# BaseBoard.net
KiCad netlist of a schematic drawn in EAGLE
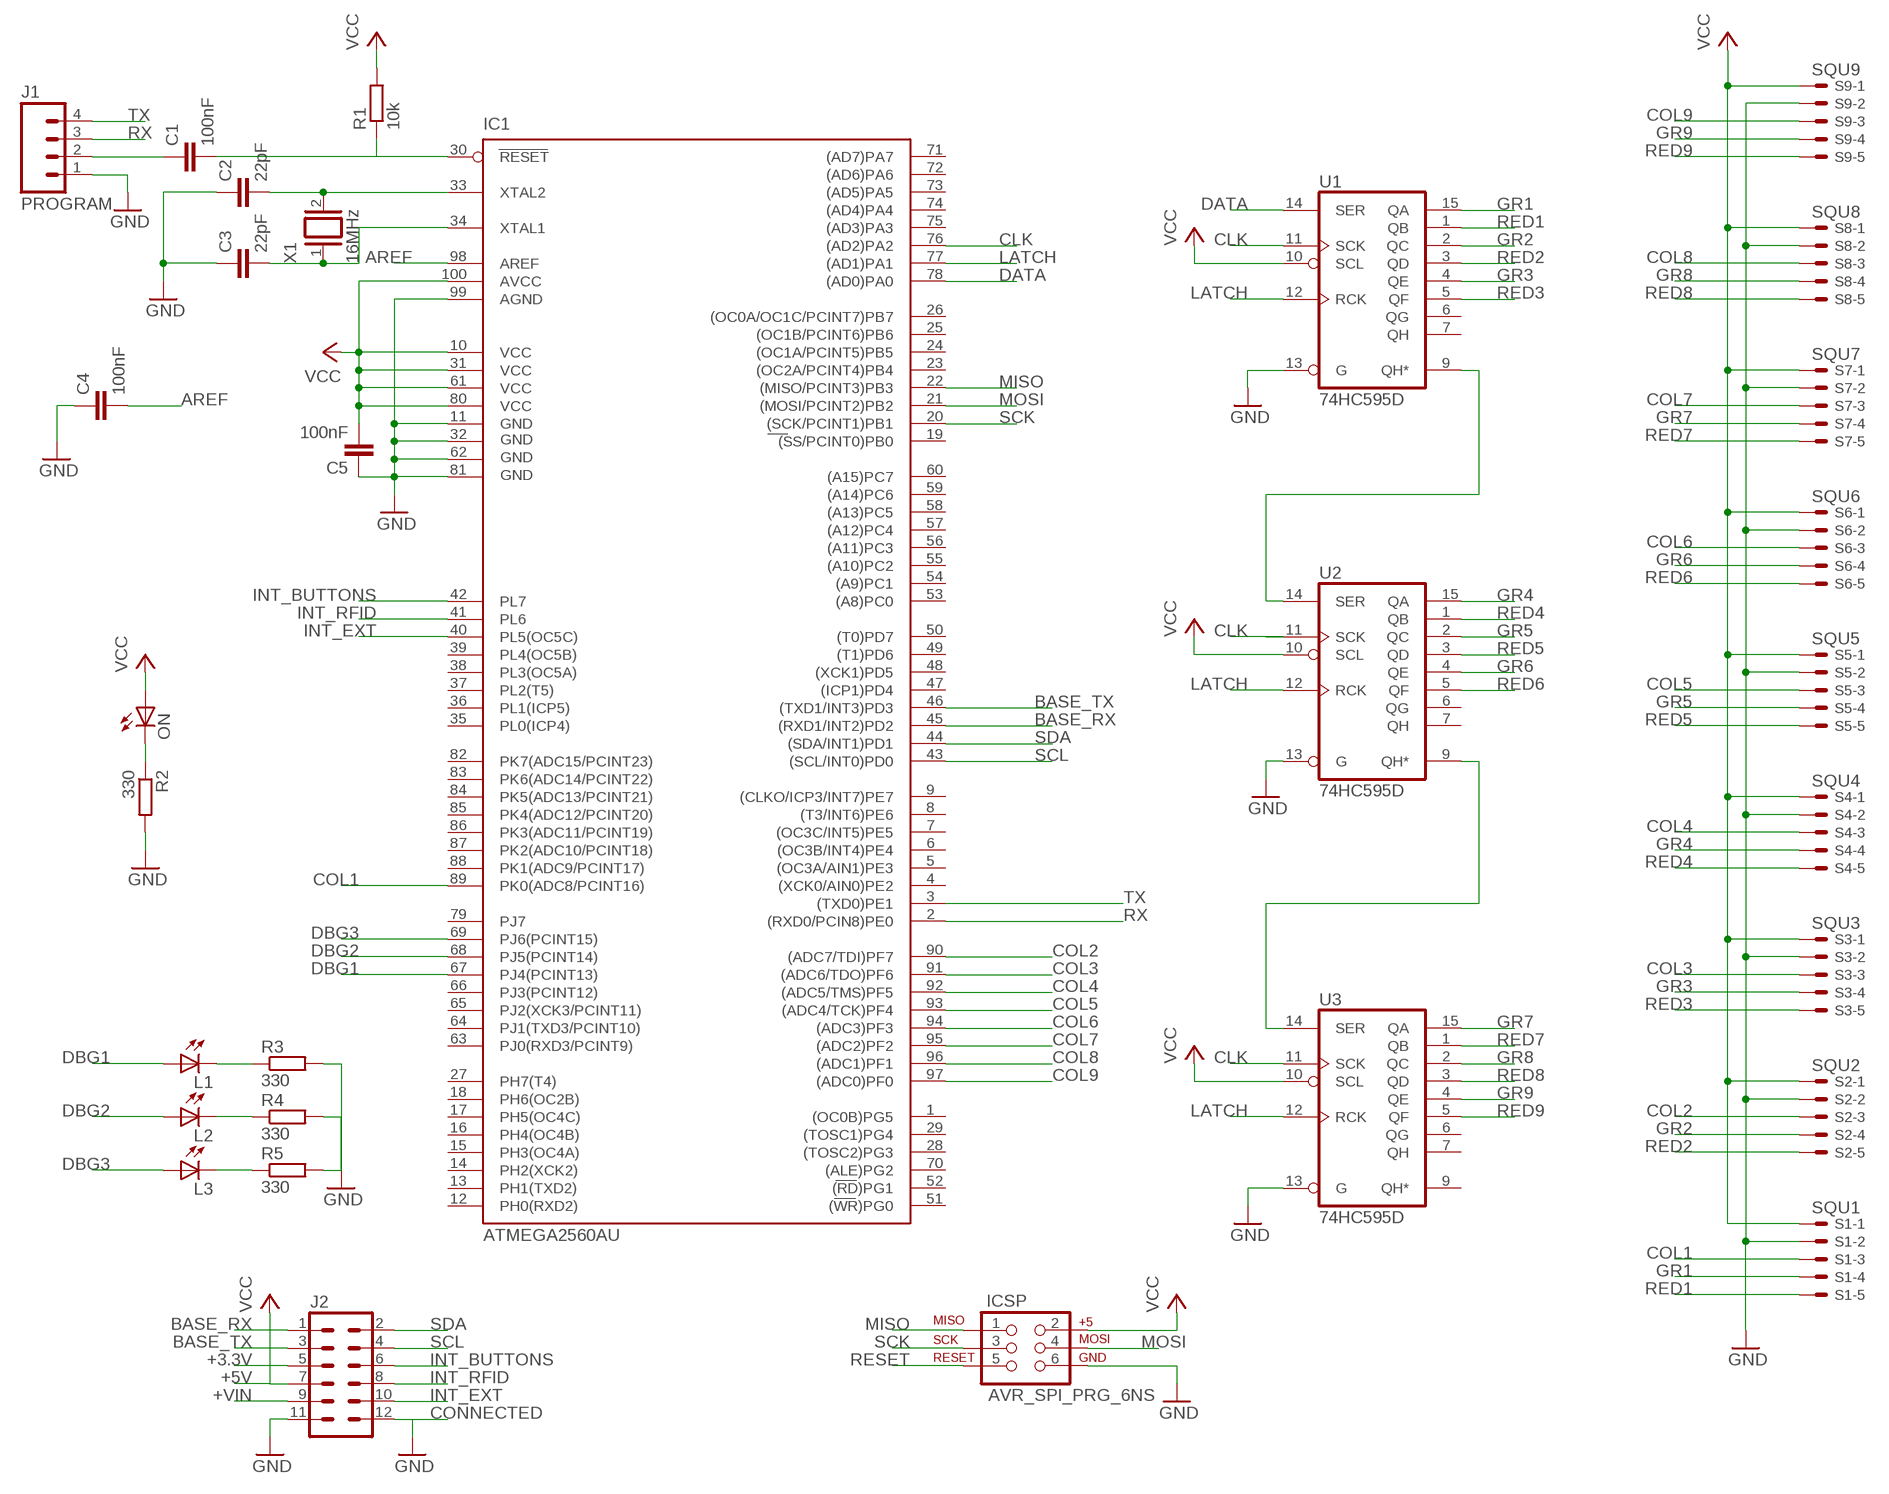
[diagram p0: schematic, sheet 1]

(export (version "E")
  (design (tool "Eeschema 10.0.6"))
  (components
    (comp (ref "C1")
      (value "100nF")
      (footprint "eagle-import:C0805")
      (libsource (lib "eagle-import") (part "C-EUC0805"))
    )
    (comp (ref "C2")
      (value "22pF")
      (footprint "eagle-import:C0805")
      (libsource (lib "eagle-import") (part "C-EUC0805"))
    )
    (comp (ref "C3")
      (value "22pF")
      (footprint "eagle-import:C0805")
      (libsource (lib "eagle-import") (part "C-EUC0805"))
    )
    (comp (ref "C4")
      (value "100nF")
      (footprint "eagle-import:C0805")
      (libsource (lib "eagle-import") (part "C-EUC0805"))
    )
    (comp (ref "C5")
      (value "100nF")
      (footprint "eagle-import:C0805")
      (libsource (lib "eagle-import") (part "C-EUC0805"))
    )
    (comp (ref "IC1")
      (value "ATMEGA2560AU")
      (footprint "eagle-import:TQFP100")
      (libsource (lib "eagle-import") (part "ATMEGA2560AU"))
    )
    (comp (ref "ICSP")
      (value "AVR_SPI_PRG_6NS")
      (footprint "eagle-import:2X3-NS")
      (libsource (lib "eagle-import") (part "AVR_SPI_PRG_6NS"))
    )
    (comp (ref "J1")
      (value "PROGRAM")
      (footprint "eagle-import:1X04")
      (libsource (lib "eagle-import") (part "M04PTH"))
    )
    (comp (ref "J2")
      (value "CON06X2-2MM")
      (footprint "eagle-import:CON06X2_2MM")
      (libsource (lib "eagle-import") (part "CON06X2-2MM"))
    )
    (comp (ref "L1")
      (value "LEDCHIP-LED0805")
      (footprint "eagle-import:CHIP-LED0805")
      (libsource (lib "eagle-import") (part "LEDCHIP-LED0805"))
    )
    (comp (ref "L2")
      (value "LEDCHIP-LED0805")
      (footprint "eagle-import:CHIP-LED0805")
      (libsource (lib "eagle-import") (part "LEDCHIP-LED0805"))
    )
    (comp (ref "L3")
      (value "LEDCHIP-LED0805")
      (footprint "eagle-import:CHIP-LED0805")
      (libsource (lib "eagle-import") (part "LEDCHIP-LED0805"))
    )
    (comp (ref "ON")
      (value "LEDCHIP-LED0805")
      (footprint "eagle-import:CHIP-LED0805")
      (libsource (lib "eagle-import") (part "LEDCHIP-LED0805"))
    )
    (comp (ref "R1")
      (value "10k")
      (footprint "eagle-import:R0805")
      (libsource (lib "eagle-import") (part "R-EU_R0805"))
    )
    (comp (ref "R2")
      (value "330")
      (footprint "eagle-import:R0805")
      (libsource (lib "eagle-import") (part "R-EU_R0805"))
    )
    (comp (ref "R3")
      (value "330")
      (footprint "eagle-import:R0805")
      (libsource (lib "eagle-import") (part "R-EU_R0805"))
    )
    (comp (ref "R4")
      (value "330")
      (footprint "eagle-import:R0805")
      (libsource (lib "eagle-import") (part "R-EU_R0805"))
    )
    (comp (ref "R5")
      (value "330")
      (footprint "eagle-import:R0805")
      (libsource (lib "eagle-import") (part "R-EU_R0805"))
    )
    (comp (ref "S1")
      (value "SQU1")
      (footprint "eagle-import:53261-05")
      (libsource (lib "eagle-import") (part "53?-05261"))
    )
    (comp (ref "S2")
      (value "SQU2")
      (footprint "eagle-import:53261-05")
      (libsource (lib "eagle-import") (part "53?-05261"))
    )
    (comp (ref "S3")
      (value "SQU3")
      (footprint "eagle-import:53261-05")
      (libsource (lib "eagle-import") (part "53?-05261"))
    )
    (comp (ref "S4")
      (value "SQU4")
      (footprint "eagle-import:53261-05")
      (libsource (lib "eagle-import") (part "53?-05261"))
    )
    (comp (ref "S5")
      (value "SQU5")
      (footprint "eagle-import:53261-05")
      (libsource (lib "eagle-import") (part "53?-05261"))
    )
    (comp (ref "S6")
      (value "SQU6")
      (footprint "eagle-import:53261-05")
      (libsource (lib "eagle-import") (part "53?-05261"))
    )
    (comp (ref "S7")
      (value "SQU7")
      (footprint "eagle-import:53261-05")
      (libsource (lib "eagle-import") (part "53?-05261"))
    )
    (comp (ref "S8")
      (value "SQU8")
      (footprint "eagle-import:53261-05")
      (libsource (lib "eagle-import") (part "53?-05261"))
    )
    (comp (ref "S9")
      (value "SQU9")
      (footprint "eagle-import:53261-05")
      (libsource (lib "eagle-import") (part "53?-05261"))
    )
    (comp (ref "U1")
      (value "74HC595D")
      (footprint "eagle-import:SO16")
      (libsource (lib "eagle-import") (part "74595DHC"))
    )
    (comp (ref "U2")
      (value "74HC595D")
      (footprint "eagle-import:SO16")
      (libsource (lib "eagle-import") (part "74595DHC"))
    )
    (comp (ref "U3")
      (value "74HC595D")
      (footprint "eagle-import:SO16")
      (libsource (lib "eagle-import") (part "74595DHC"))
    )
    (comp (ref "X1")
      (value "16MHz")
      (footprint "eagle-import:QS")
      (libsource (lib "eagle-import") (part "XTAL/S"))
    )
  )
  (nets
    (net (code "1") (name "/+3.3V") (class "Default")
      (node (ref "J2") (pin "5") (pinfunction "5_5") (pintype "passive"))
    )
    (net (code "2") (name "/+VIN") (class "Default")
      (node (ref "J2") (pin "9") (pinfunction "9_9") (pintype "passive"))
    )
    (net (code "3") (name "/AREF") (class "Default")
      (node (ref "C4") (pin "2") (pinfunction "2_2") (pintype "passive"))
      (node (ref "IC1") (pin "98") (pinfunction "AREF_98") (pintype "bidirectional"))
    )
    (net (code "4") (name "/BASE_RX") (class "Default")
      (node (ref "IC1") (pin "45") (pinfunction "(RXD1/INT2)PD2_45") (pintype "bidirectional"))
      (node (ref "J2") (pin "1") (pinfunction "1_1") (pintype "passive"))
    )
    (net (code "5") (name "/BASE_TX") (class "Default")
      (node (ref "IC1") (pin "46") (pinfunction "(TXD1/INT3)PD3_46") (pintype "bidirectional"))
      (node (ref "J2") (pin "3") (pinfunction "3_3") (pintype "passive"))
    )
    (net (code "6") (name "/CLK") (class "Default")
      (node (ref "IC1") (pin "76") (pinfunction "(AD2)PA2_76") (pintype "bidirectional"))
      (node (ref "U1") (pin "11") (pinfunction "SCK_11") (pintype "input"))
      (node (ref "U2") (pin "11") (pinfunction "SCK_11") (pintype "input"))
      (node (ref "U3") (pin "11") (pinfunction "SCK_11") (pintype "input"))
    )
    (net (code "7") (name "/COL1") (class "Default")
      (node (ref "IC1") (pin "89") (pinfunction "PK0(ADC8/PCINT16)_89") (pintype "bidirectional"))
      (node (ref "S1") (pin "3") (pinfunction "S_3") (pintype "passive"))
    )
    (net (code "8") (name "/COL2") (class "Default")
      (node (ref "IC1") (pin "90") (pinfunction "(ADC7/TDI)PF7_90") (pintype "bidirectional"))
      (node (ref "S2") (pin "3") (pinfunction "S_3") (pintype "passive"))
    )
    (net (code "9") (name "/COL3") (class "Default")
      (node (ref "IC1") (pin "91") (pinfunction "(ADC6/TDO)PF6_91") (pintype "bidirectional"))
      (node (ref "S3") (pin "3") (pinfunction "S_3") (pintype "passive"))
    )
    (net (code "10") (name "/COL4") (class "Default")
      (node (ref "IC1") (pin "92") (pinfunction "(ADC5/TMS)PF5_92") (pintype "bidirectional"))
      (node (ref "S4") (pin "3") (pinfunction "S_3") (pintype "passive"))
    )
    (net (code "11") (name "/COL5") (class "Default")
      (node (ref "IC1") (pin "93") (pinfunction "(ADC4/TCK)PF4_93") (pintype "bidirectional"))
      (node (ref "S5") (pin "3") (pinfunction "S_3") (pintype "passive"))
    )
    (net (code "12") (name "/COL6") (class "Default")
      (node (ref "IC1") (pin "94") (pinfunction "(ADC3)PF3_94") (pintype "bidirectional"))
      (node (ref "S6") (pin "3") (pinfunction "S_3") (pintype "passive"))
    )
    (net (code "13") (name "/COL7") (class "Default")
      (node (ref "IC1") (pin "95") (pinfunction "(ADC2)PF2_95") (pintype "bidirectional"))
      (node (ref "S7") (pin "3") (pinfunction "S_3") (pintype "passive"))
    )
    (net (code "14") (name "/COL8") (class "Default")
      (node (ref "IC1") (pin "96") (pinfunction "(ADC1)PF1_96") (pintype "bidirectional"))
      (node (ref "S8") (pin "3") (pinfunction "S_3") (pintype "passive"))
    )
    (net (code "15") (name "/COL9") (class "Default")
      (node (ref "IC1") (pin "97") (pinfunction "(ADC0)PF0_97") (pintype "bidirectional"))
      (node (ref "S9") (pin "3") (pinfunction "S_3") (pintype "passive"))
    )
    (net (code "16") (name "/DATA") (class "Default")
      (node (ref "IC1") (pin "78") (pinfunction "(AD0)PA0_78") (pintype "bidirectional"))
      (node (ref "U1") (pin "14") (pinfunction "SER_14") (pintype "input"))
    )
    (net (code "17") (name "/DBG1") (class "Default")
      (node (ref "IC1") (pin "67") (pinfunction "PJ4(PCINT13)_67") (pintype "bidirectional"))
      (node (ref "L1") (pin "A") (pinfunction "A_A") (pintype "passive"))
    )
    (net (code "18") (name "/DBG2") (class "Default")
      (node (ref "IC1") (pin "68") (pinfunction "PJ5(PCINT14)_68") (pintype "bidirectional"))
      (node (ref "L2") (pin "A") (pinfunction "A_A") (pintype "passive"))
    )
    (net (code "19") (name "/DBG3") (class "Default")
      (node (ref "IC1") (pin "69") (pinfunction "PJ6(PCINT15)_69") (pintype "bidirectional"))
      (node (ref "L3") (pin "A") (pinfunction "A_A") (pintype "passive"))
    )
    (net (code "20") (name "/GR1") (class "Default")
      (node (ref "S1") (pin "4") (pinfunction "S_4") (pintype "passive"))
      (node (ref "U1") (pin "15") (pinfunction "QA_15") (pintype "tri_state"))
    )
    (net (code "21") (name "/GR2") (class "Default")
      (node (ref "S2") (pin "4") (pinfunction "S_4") (pintype "passive"))
      (node (ref "U1") (pin "2") (pinfunction "QC_2") (pintype "tri_state"))
    )
    (net (code "22") (name "/GR3") (class "Default")
      (node (ref "S3") (pin "4") (pinfunction "S_4") (pintype "passive"))
      (node (ref "U1") (pin "4") (pinfunction "QE_4") (pintype "tri_state"))
    )
    (net (code "23") (name "/GR4") (class "Default")
      (node (ref "S4") (pin "4") (pinfunction "S_4") (pintype "passive"))
      (node (ref "U2") (pin "15") (pinfunction "QA_15") (pintype "tri_state"))
    )
    (net (code "24") (name "/GR5") (class "Default")
      (node (ref "S5") (pin "4") (pinfunction "S_4") (pintype "passive"))
      (node (ref "U2") (pin "2") (pinfunction "QC_2") (pintype "tri_state"))
    )
    (net (code "25") (name "/GR6") (class "Default")
      (node (ref "S6") (pin "4") (pinfunction "S_4") (pintype "passive"))
      (node (ref "U2") (pin "4") (pinfunction "QE_4") (pintype "tri_state"))
    )
    (net (code "26") (name "/GR7") (class "Default")
      (node (ref "S7") (pin "4") (pinfunction "S_4") (pintype "passive"))
      (node (ref "U3") (pin "15") (pinfunction "QA_15") (pintype "tri_state"))
    )
    (net (code "27") (name "/GR8") (class "Default")
      (node (ref "S8") (pin "4") (pinfunction "S_4") (pintype "passive"))
      (node (ref "U3") (pin "2") (pinfunction "QC_2") (pintype "tri_state"))
    )
    (net (code "28") (name "/GR9") (class "Default")
      (node (ref "S9") (pin "4") (pinfunction "S_4") (pintype "passive"))
      (node (ref "U3") (pin "4") (pinfunction "QE_4") (pintype "tri_state"))
    )
    (net (code "29") (name "/INT_BUTTONS") (class "Default")
      (node (ref "IC1") (pin "42") (pinfunction "PL7_42") (pintype "bidirectional"))
      (node (ref "J2") (pin "6") (pinfunction "6_6") (pintype "passive"))
    )
    (net (code "30") (name "/INT_EXT") (class "Default")
      (node (ref "IC1") (pin "40") (pinfunction "PL5(OC5C)_40") (pintype "bidirectional"))
      (node (ref "J2") (pin "10") (pinfunction "10_10") (pintype "passive"))
    )
    (net (code "31") (name "/INT_RFID") (class "Default")
      (node (ref "IC1") (pin "41") (pinfunction "PL6_41") (pintype "bidirectional"))
      (node (ref "J2") (pin "8") (pinfunction "8_8") (pintype "passive"))
    )
    (net (code "32") (name "/LATCH") (class "Default")
      (node (ref "IC1") (pin "77") (pinfunction "(AD1)PA1_77") (pintype "bidirectional"))
      (node (ref "U1") (pin "12") (pinfunction "RCK_12") (pintype "input"))
      (node (ref "U2") (pin "12") (pinfunction "RCK_12") (pintype "input"))
      (node (ref "U3") (pin "12") (pinfunction "RCK_12") (pintype "input"))
    )
    (net (code "33") (name "/MISO") (class "Default")
      (node (ref "IC1") (pin "22") (pinfunction "(MISO/PCINT3)PB3_22") (pintype "bidirectional"))
      (node (ref "ICSP") (pin "1") (pinfunction "1_1") (pintype "passive"))
    )
    (net (code "34") (name "/MOSI") (class "Default")
      (node (ref "IC1") (pin "21") (pinfunction "(MOSI/PCINT2)PB2_21") (pintype "bidirectional"))
      (node (ref "ICSP") (pin "4") (pinfunction "4_4") (pintype "passive"))
    )
    (net (code "35") (name "/RED1") (class "Default")
      (node (ref "S1") (pin "5") (pinfunction "S_5") (pintype "passive"))
      (node (ref "U1") (pin "1") (pinfunction "QB_1") (pintype "tri_state"))
    )
    (net (code "36") (name "/RED2") (class "Default")
      (node (ref "S2") (pin "5") (pinfunction "S_5") (pintype "passive"))
      (node (ref "U1") (pin "3") (pinfunction "QD_3") (pintype "tri_state"))
    )
    (net (code "37") (name "/RED3") (class "Default")
      (node (ref "S3") (pin "5") (pinfunction "S_5") (pintype "passive"))
      (node (ref "U1") (pin "5") (pinfunction "QF_5") (pintype "tri_state"))
    )
    (net (code "38") (name "/RED4") (class "Default")
      (node (ref "S4") (pin "5") (pinfunction "S_5") (pintype "passive"))
      (node (ref "U2") (pin "1") (pinfunction "QB_1") (pintype "tri_state"))
    )
    (net (code "39") (name "/RED5") (class "Default")
      (node (ref "S5") (pin "5") (pinfunction "S_5") (pintype "passive"))
      (node (ref "U2") (pin "3") (pinfunction "QD_3") (pintype "tri_state"))
    )
    (net (code "40") (name "/RED6") (class "Default")
      (node (ref "S6") (pin "5") (pinfunction "S_5") (pintype "passive"))
      (node (ref "U2") (pin "5") (pinfunction "QF_5") (pintype "tri_state"))
    )
    (net (code "41") (name "/RED7") (class "Default")
      (node (ref "S7") (pin "5") (pinfunction "S_5") (pintype "passive"))
      (node (ref "U3") (pin "1") (pinfunction "QB_1") (pintype "tri_state"))
    )
    (net (code "42") (name "/RED8") (class "Default")
      (node (ref "S8") (pin "5") (pinfunction "S_5") (pintype "passive"))
      (node (ref "U3") (pin "3") (pinfunction "QD_3") (pintype "tri_state"))
    )
    (net (code "43") (name "/RED9") (class "Default")
      (node (ref "S9") (pin "5") (pinfunction "S_5") (pintype "passive"))
      (node (ref "U3") (pin "5") (pinfunction "QF_5") (pintype "tri_state"))
    )
    (net (code "44") (name "/RESET") (class "Default")
      (node (ref "C1") (pin "2") (pinfunction "2_2") (pintype "passive"))
      (node (ref "IC1") (pin "30") (pinfunction "RESET_30") (pintype "input"))
      (node (ref "ICSP") (pin "5") (pinfunction "5_5") (pintype "passive"))
      (node (ref "R1") (pin "1") (pinfunction "1_1") (pintype "passive"))
    )
    (net (code "45") (name "/RX") (class "Default")
      (node (ref "IC1") (pin "2") (pinfunction "(RXD0/PCIN8)PE0_2") (pintype "bidirectional"))
      (node (ref "J1") (pin "3") (pinfunction "3_3") (pintype "passive"))
    )
    (net (code "46") (name "/SCK") (class "Default")
      (node (ref "IC1") (pin "20") (pinfunction "(SCK/PCINT1)PB1_20") (pintype "bidirectional"))
      (node (ref "ICSP") (pin "3") (pinfunction "3_3") (pintype "passive"))
    )
    (net (code "47") (name "/SCL") (class "Default")
      (node (ref "IC1") (pin "43") (pinfunction "(SCL/INT0)PD0_43") (pintype "bidirectional"))
      (node (ref "J2") (pin "4") (pinfunction "4_4") (pintype "passive"))
    )
    (net (code "48") (name "/SDA") (class "Default")
      (node (ref "IC1") (pin "44") (pinfunction "(SDA/INT1)PD1_44") (pintype "bidirectional"))
      (node (ref "J2") (pin "2") (pinfunction "2_2") (pintype "passive"))
    )
    (net (code "49") (name "/TX") (class "Default")
      (node (ref "IC1") (pin "3") (pinfunction "(TXD0)PE1_3") (pintype "bidirectional"))
      (node (ref "J1") (pin "4") (pinfunction "4_4") (pintype "passive"))
    )
    (net (code "50") (name "GND") (class "Default")
      (node (ref "C2") (pin "1") (pinfunction "1_1") (pintype "passive"))
      (node (ref "C3") (pin "1") (pinfunction "1_1") (pintype "passive"))
      (node (ref "C4") (pin "1") (pinfunction "1_1") (pintype "passive"))
      (node (ref "C5") (pin "1") (pinfunction "1_1") (pintype "passive"))
      (node (ref "IC1") (pin "11") (pinfunction "GND_11") (pintype "power_in"))
      (node (ref "IC1") (pin "32") (pinfunction "GND1_32") (pintype "power_in"))
      (node (ref "IC1") (pin "62") (pinfunction "GND2_62") (pintype "power_in"))
      (node (ref "IC1") (pin "81") (pinfunction "GND3_81") (pintype "power_in"))
      (node (ref "IC1") (pin "99") (pinfunction "AGND_99") (pintype "power_in"))
      (node (ref "ICSP") (pin "6") (pinfunction "6_6") (pintype "passive"))
      (node (ref "J1") (pin "1") (pinfunction "1_1") (pintype "passive"))
      (node (ref "J2") (pin "11") (pinfunction "11_11") (pintype "passive"))
      (node (ref "J2") (pin "12") (pinfunction "12_12") (pintype "passive"))
      (node (ref "R2") (pin "2") (pinfunction "2_2") (pintype "passive"))
      (node (ref "R3") (pin "2") (pinfunction "2_2") (pintype "passive"))
      (node (ref "R4") (pin "2") (pinfunction "2_2") (pintype "passive"))
      (node (ref "R5") (pin "2") (pinfunction "2_2") (pintype "passive"))
      (node (ref "S1") (pin "2") (pinfunction "S_2") (pintype "passive"))
      (node (ref "S2") (pin "2") (pinfunction "S_2") (pintype "passive"))
      (node (ref "S3") (pin "2") (pinfunction "S_2") (pintype "passive"))
      (node (ref "S4") (pin "2") (pinfunction "S_2") (pintype "passive"))
      (node (ref "S5") (pin "2") (pinfunction "S_2") (pintype "passive"))
      (node (ref "S6") (pin "2") (pinfunction "S_2") (pintype "passive"))
      (node (ref "S7") (pin "2") (pinfunction "S_2") (pintype "passive"))
      (node (ref "S8") (pin "2") (pinfunction "S_2") (pintype "passive"))
      (node (ref "S9") (pin "2") (pinfunction "S_2") (pintype "passive"))
      (node (ref "U1") (pin "13") (pinfunction "G_13") (pintype "input"))
      (node (ref "U2") (pin "13") (pinfunction "G_13") (pintype "input"))
      (node (ref "U3") (pin "13") (pinfunction "G_13") (pintype "input"))
    )
    (net (code "51") (name "Net-(C1-Pad1)") (class "Default")
      (node (ref "C1") (pin "1") (pinfunction "1_1") (pintype "passive"))
      (node (ref "J1") (pin "2") (pinfunction "2_2") (pintype "passive"))
    )
    (net (code "52") (name "Net-(IC1-XTAL1)") (class "Default")
      (node (ref "C3") (pin "2") (pinfunction "2_2") (pintype "passive"))
      (node (ref "IC1") (pin "34") (pinfunction "XTAL1_34") (pintype "input"))
      (node (ref "X1") (pin "1") (pinfunction "1_1") (pintype "passive"))
    )
    (net (code "53") (name "Net-(IC1-XTAL2)") (class "Default")
      (node (ref "C2") (pin "2") (pinfunction "2_2") (pintype "passive"))
      (node (ref "IC1") (pin "33") (pinfunction "XTAL2_33") (pintype "output"))
      (node (ref "X1") (pin "2") (pinfunction "2_2") (pintype "passive"))
    )
    (net (code "54") (name "Net-(L1-PadC)") (class "Default")
      (node (ref "L1") (pin "C") (pinfunction "C_C") (pintype "passive"))
      (node (ref "R3") (pin "1") (pinfunction "1_1") (pintype "passive"))
    )
    (net (code "55") (name "Net-(L2-PadC)") (class "Default")
      (node (ref "L2") (pin "C") (pinfunction "C_C") (pintype "passive"))
      (node (ref "R4") (pin "1") (pinfunction "1_1") (pintype "passive"))
    )
    (net (code "56") (name "Net-(L3-PadC)") (class "Default")
      (node (ref "L3") (pin "C") (pinfunction "C_C") (pintype "passive"))
      (node (ref "R5") (pin "1") (pinfunction "1_1") (pintype "passive"))
    )
    (net (code "57") (name "Net-(ON-PadC)") (class "Default")
      (node (ref "ON") (pin "C") (pinfunction "C_C") (pintype "passive"))
      (node (ref "R2") (pin "1") (pinfunction "1_1") (pintype "passive"))
    )
    (net (code "58") (name "Net-(U1A-QH*)") (class "Default")
      (node (ref "U1") (pin "9") (pinfunction "QH*_9") (pintype "tri_state"))
      (node (ref "U2") (pin "14") (pinfunction "SER_14") (pintype "input"))
    )
    (net (code "59") (name "Net-(U2A-QH*)") (class "Default")
      (node (ref "U2") (pin "9") (pinfunction "QH*_9") (pintype "tri_state"))
      (node (ref "U3") (pin "14") (pinfunction "SER_14") (pintype "input"))
    )
    (net (code "60") (name "VCC") (class "Default")
      (node (ref "C5") (pin "2") (pinfunction "2_2") (pintype "passive"))
      (node (ref "IC1") (pin "10") (pinfunction "VCC_10") (pintype "power_in"))
      (node (ref "IC1") (pin "100") (pinfunction "AVCC_100") (pintype "power_in"))
      (node (ref "IC1") (pin "31") (pinfunction "VCC1_31") (pintype "power_in"))
      (node (ref "IC1") (pin "61") (pinfunction "VCC2_61") (pintype "power_in"))
      (node (ref "IC1") (pin "80") (pinfunction "VCC3_80") (pintype "power_in"))
      (node (ref "ICSP") (pin "2") (pinfunction "2_2") (pintype "passive"))
      (node (ref "J2") (pin "7") (pinfunction "7_7") (pintype "passive"))
      (node (ref "ON") (pin "A") (pinfunction "A_A") (pintype "passive"))
      (node (ref "R1") (pin "2") (pinfunction "2_2") (pintype "passive"))
      (node (ref "S1") (pin "1") (pinfunction "S_1") (pintype "passive"))
      (node (ref "S2") (pin "1") (pinfunction "S_1") (pintype "passive"))
      (node (ref "S3") (pin "1") (pinfunction "S_1") (pintype "passive"))
      (node (ref "S4") (pin "1") (pinfunction "S_1") (pintype "passive"))
      (node (ref "S5") (pin "1") (pinfunction "S_1") (pintype "passive"))
      (node (ref "S6") (pin "1") (pinfunction "S_1") (pintype "passive"))
      (node (ref "S7") (pin "1") (pinfunction "S_1") (pintype "passive"))
      (node (ref "S8") (pin "1") (pinfunction "S_1") (pintype "passive"))
      (node (ref "S9") (pin "1") (pinfunction "S_1") (pintype "passive"))
      (node (ref "U1") (pin "10") (pinfunction "SCL_10") (pintype "input"))
      (node (ref "U2") (pin "10") (pinfunction "SCL_10") (pintype "input"))
      (node (ref "U3") (pin "10") (pinfunction "SCL_10") (pintype "input"))
    )
    (net (code "61") (name "unconnected-(IC1-(A8)PC0-Pad53)") (class "Default")
      (node (ref "IC1") (pin "53") (pinfunction "(A8)PC0_53") (pintype "bidirectional"))
    )
    (net (code "62") (name "unconnected-(IC1-(A9)PC1-Pad54)") (class "Default")
      (node (ref "IC1") (pin "54") (pinfunction "(A9)PC1_54") (pintype "bidirectional"))
    )
    (net (code "63") (name "unconnected-(IC1-(A10)PC2-Pad55)") (class "Default")
      (node (ref "IC1") (pin "55") (pinfunction "(A10)PC2_55") (pintype "bidirectional"))
    )
    (net (code "64") (name "unconnected-(IC1-(A11)PC3-Pad56)") (class "Default")
      (node (ref "IC1") (pin "56") (pinfunction "(A11)PC3_56") (pintype "bidirectional"))
    )
    (net (code "65") (name "unconnected-(IC1-(A12)PC4-Pad57)") (class "Default")
      (node (ref "IC1") (pin "57") (pinfunction "(A12)PC4_57") (pintype "bidirectional"))
    )
    (net (code "66") (name "unconnected-(IC1-(A13)PC5-Pad58)") (class "Default")
      (node (ref "IC1") (pin "58") (pinfunction "(A13)PC5_58") (pintype "bidirectional"))
    )
    (net (code "67") (name "unconnected-(IC1-(A14)PC6-Pad59)") (class "Default")
      (node (ref "IC1") (pin "59") (pinfunction "(A14)PC6_59") (pintype "bidirectional"))
    )
    (net (code "68") (name "unconnected-(IC1-(A15)PC7-Pad60)") (class "Default")
      (node (ref "IC1") (pin "60") (pinfunction "(A15)PC7_60") (pintype "bidirectional"))
    )
    (net (code "69") (name "unconnected-(IC1-(AD3)PA3-Pad75)") (class "Default")
      (node (ref "IC1") (pin "75") (pinfunction "(AD3)PA3_75") (pintype "bidirectional"))
    )
    (net (code "70") (name "unconnected-(IC1-(AD4)PA4-Pad74)") (class "Default")
      (node (ref "IC1") (pin "74") (pinfunction "(AD4)PA4_74") (pintype "bidirectional"))
    )
    (net (code "71") (name "unconnected-(IC1-(AD5)PA5-Pad73)") (class "Default")
      (node (ref "IC1") (pin "73") (pinfunction "(AD5)PA5_73") (pintype "bidirectional"))
    )
    (net (code "72") (name "unconnected-(IC1-(AD6)PA6-Pad72)") (class "Default")
      (node (ref "IC1") (pin "72") (pinfunction "(AD6)PA6_72") (pintype "bidirectional"))
    )
    (net (code "73") (name "unconnected-(IC1-(AD7)PA7-Pad71)") (class "Default")
      (node (ref "IC1") (pin "71") (pinfunction "(AD7)PA7_71") (pintype "bidirectional"))
    )
    (net (code "74") (name "unconnected-(IC1-(ALE)PG2-Pad70)") (class "Default")
      (node (ref "IC1") (pin "70") (pinfunction "(ALE)PG2_70") (pintype "bidirectional"))
    )
    (net (code "75") (name "unconnected-(IC1-(CLKO{slash}ICP3{slash}INT7)PE7-Pad9)") (class "Default")
      (node (ref "IC1") (pin "9") (pinfunction "(CLKO/ICP3/INT7)PE7_9") (pintype "bidirectional"))
    )
    (net (code "76") (name "unconnected-(IC1-(ICP1)PD4-Pad47)") (class "Default")
      (node (ref "IC1") (pin "47") (pinfunction "(ICP1)PD4_47") (pintype "bidirectional"))
    )
    (net (code "77") (name "unconnected-(IC1-(OC0A{slash}OC1C{slash}PCINT7)PB7-Pad26)") (class "Default")
      (node (ref "IC1") (pin "26") (pinfunction "(OC0A/OC1C/PCINT7)PB7_26") (pintype "bidirectional"))
    )
    (net (code "78") (name "unconnected-(IC1-(OC0B)PG5-Pad1)") (class "Default")
      (node (ref "IC1") (pin "1") (pinfunction "(OC0B)PG5_1") (pintype "bidirectional"))
    )
    (net (code "79") (name "unconnected-(IC1-(OC1A{slash}PCINT5)PB5-Pad24)") (class "Default")
      (node (ref "IC1") (pin "24") (pinfunction "(OC1A/PCINT5)PB5_24") (pintype "bidirectional"))
    )
    (net (code "80") (name "unconnected-(IC1-(OC1B{slash}PCINT6)PB6-Pad25)") (class "Default")
      (node (ref "IC1") (pin "25") (pinfunction "(OC1B/PCINT6)PB6_25") (pintype "bidirectional"))
    )
    (net (code "81") (name "unconnected-(IC1-(OC2A{slash}PCINT4)PB4-Pad23)") (class "Default")
      (node (ref "IC1") (pin "23") (pinfunction "(OC2A/PCINT4)PB4_23") (pintype "bidirectional"))
    )
    (net (code "82") (name "unconnected-(IC1-(OC3A{slash}AIN1)PE3-Pad5)") (class "Default")
      (node (ref "IC1") (pin "5") (pinfunction "(OC3A/AIN1)PE3_5") (pintype "bidirectional"))
    )
    (net (code "83") (name "unconnected-(IC1-(OC3B{slash}INT4)PE4-Pad6)") (class "Default")
      (node (ref "IC1") (pin "6") (pinfunction "(OC3B/INT4)PE4_6") (pintype "bidirectional"))
    )
    (net (code "84") (name "unconnected-(IC1-(OC3C{slash}INT5)PE5-Pad7)") (class "Default")
      (node (ref "IC1") (pin "7") (pinfunction "(OC3C/INT5)PE5_7") (pintype "bidirectional"))
    )
    (net (code "85") (name "unconnected-(IC1-(RD)PG1-Pad52)") (class "Default")
      (node (ref "IC1") (pin "52") (pinfunction "(RD)PG1_52") (pintype "bidirectional"))
    )
    (net (code "86") (name "unconnected-(IC1-(SS{slash}PCINT0)PB0-Pad19)") (class "Default")
      (node (ref "IC1") (pin "19") (pinfunction "(SS/PCINT0)PB0_19") (pintype "bidirectional"))
    )
    (net (code "87") (name "unconnected-(IC1-(T0)PD7-Pad50)") (class "Default")
      (node (ref "IC1") (pin "50") (pinfunction "(T0)PD7_50") (pintype "bidirectional"))
    )
    (net (code "88") (name "unconnected-(IC1-(T1)PD6-Pad49)") (class "Default")
      (node (ref "IC1") (pin "49") (pinfunction "(T1)PD6_49") (pintype "bidirectional"))
    )
    (net (code "89") (name "unconnected-(IC1-(T3{slash}INT6)PE6-Pad8)") (class "Default")
      (node (ref "IC1") (pin "8") (pinfunction "(T3/INT6)PE6_8") (pintype "bidirectional"))
    )
    (net (code "90") (name "unconnected-(IC1-(TOSC1)PG4-Pad29)") (class "Default")
      (node (ref "IC1") (pin "29") (pinfunction "(TOSC1)PG4_29") (pintype "bidirectional"))
    )
    (net (code "91") (name "unconnected-(IC1-(TOSC2)PG3-Pad28)") (class "Default")
      (node (ref "IC1") (pin "28") (pinfunction "(TOSC2)PG3_28") (pintype "bidirectional"))
    )
    (net (code "92") (name "unconnected-(IC1-(WR)PG0-Pad51)") (class "Default")
      (node (ref "IC1") (pin "51") (pinfunction "(WR)PG0_51") (pintype "bidirectional"))
    )
    (net (code "93") (name "unconnected-(IC1-(XCK0{slash}AIN0)PE2-Pad4)") (class "Default")
      (node (ref "IC1") (pin "4") (pinfunction "(XCK0/AIN0)PE2_4") (pintype "bidirectional"))
    )
    (net (code "94") (name "unconnected-(IC1-(XCK1)PD5-Pad48)") (class "Default")
      (node (ref "IC1") (pin "48") (pinfunction "(XCK1)PD5_48") (pintype "bidirectional"))
    )
    (net (code "95") (name "unconnected-(IC1-PH0(RXD2)-Pad12)") (class "Default")
      (node (ref "IC1") (pin "12") (pinfunction "PH0(RXD2)_12") (pintype "bidirectional"))
    )
    (net (code "96") (name "unconnected-(IC1-PH1(TXD2)-Pad13)") (class "Default")
      (node (ref "IC1") (pin "13") (pinfunction "PH1(TXD2)_13") (pintype "bidirectional"))
    )
    (net (code "97") (name "unconnected-(IC1-PH2(XCK2)-Pad14)") (class "Default")
      (node (ref "IC1") (pin "14") (pinfunction "PH2(XCK2)_14") (pintype "bidirectional"))
    )
    (net (code "98") (name "unconnected-(IC1-PH3(OC4A)-Pad15)") (class "Default")
      (node (ref "IC1") (pin "15") (pinfunction "PH3(OC4A)_15") (pintype "bidirectional"))
    )
    (net (code "99") (name "unconnected-(IC1-PH4(OC4B)-Pad16)") (class "Default")
      (node (ref "IC1") (pin "16") (pinfunction "PH4(OC4B)_16") (pintype "bidirectional"))
    )
    (net (code "100") (name "unconnected-(IC1-PH5(OC4C)-Pad17)") (class "Default")
      (node (ref "IC1") (pin "17") (pinfunction "PH5(OC4C)_17") (pintype "bidirectional"))
    )
    (net (code "101") (name "unconnected-(IC1-PH6(OC2B)-Pad18)") (class "Default")
      (node (ref "IC1") (pin "18") (pinfunction "PH6(OC2B)_18") (pintype "bidirectional"))
    )
    (net (code "102") (name "unconnected-(IC1-PH7(T4)-Pad27)") (class "Default")
      (node (ref "IC1") (pin "27") (pinfunction "PH7(T4)_27") (pintype "bidirectional"))
    )
    (net (code "103") (name "unconnected-(IC1-PJ0(RXD3{slash}PCINT9)-Pad63)") (class "Default")
      (node (ref "IC1") (pin "63") (pinfunction "PJ0(RXD3/PCINT9)_63") (pintype "bidirectional"))
    )
    (net (code "104") (name "unconnected-(IC1-PJ1(TXD3{slash}PCINT10)-Pad64)") (class "Default")
      (node (ref "IC1") (pin "64") (pinfunction "PJ1(TXD3/PCINT10)_64") (pintype "bidirectional"))
    )
    (net (code "105") (name "unconnected-(IC1-PJ2(XCK3{slash}PCINT11)-Pad65)") (class "Default")
      (node (ref "IC1") (pin "65") (pinfunction "PJ2(XCK3/PCINT11)_65") (pintype "bidirectional"))
    )
    (net (code "106") (name "unconnected-(IC1-PJ3(PCINT12)-Pad66)") (class "Default")
      (node (ref "IC1") (pin "66") (pinfunction "PJ3(PCINT12)_66") (pintype "bidirectional"))
    )
    (net (code "107") (name "unconnected-(IC1-PJ7-Pad79)") (class "Default")
      (node (ref "IC1") (pin "79") (pinfunction "PJ7_79") (pintype "bidirectional"))
    )
    (net (code "108") (name "unconnected-(IC1-PK1(ADC9{slash}PCINT17)-Pad88)") (class "Default")
      (node (ref "IC1") (pin "88") (pinfunction "PK1(ADC9/PCINT17)_88") (pintype "bidirectional"))
    )
    (net (code "109") (name "unconnected-(IC1-PK2(ADC10{slash}PCINT18)-Pad87)") (class "Default")
      (node (ref "IC1") (pin "87") (pinfunction "PK2(ADC10/PCINT18)_87") (pintype "bidirectional"))
    )
    (net (code "110") (name "unconnected-(IC1-PK3(ADC11{slash}PCINT19)-Pad86)") (class "Default")
      (node (ref "IC1") (pin "86") (pinfunction "PK3(ADC11/PCINT19)_86") (pintype "bidirectional"))
    )
    (net (code "111") (name "unconnected-(IC1-PK4(ADC12{slash}PCINT20)-Pad85)") (class "Default")
      (node (ref "IC1") (pin "85") (pinfunction "PK4(ADC12/PCINT20)_85") (pintype "bidirectional"))
    )
    (net (code "112") (name "unconnected-(IC1-PK5(ADC13{slash}PCINT21)-Pad84)") (class "Default")
      (node (ref "IC1") (pin "84") (pinfunction "PK5(ADC13/PCINT21)_84") (pintype "bidirectional"))
    )
    (net (code "113") (name "unconnected-(IC1-PK6(ADC14{slash}PCINT22)-Pad83)") (class "Default")
      (node (ref "IC1") (pin "83") (pinfunction "PK6(ADC14/PCINT22)_83") (pintype "bidirectional"))
    )
    (net (code "114") (name "unconnected-(IC1-PK7(ADC15{slash}PCINT23)-Pad82)") (class "Default")
      (node (ref "IC1") (pin "82") (pinfunction "PK7(ADC15/PCINT23)_82") (pintype "bidirectional"))
    )
    (net (code "115") (name "unconnected-(IC1-PL0(ICP4)-Pad35)") (class "Default")
      (node (ref "IC1") (pin "35") (pinfunction "PL0(ICP4)_35") (pintype "bidirectional"))
    )
    (net (code "116") (name "unconnected-(IC1-PL1(ICP5)-Pad36)") (class "Default")
      (node (ref "IC1") (pin "36") (pinfunction "PL1(ICP5)_36") (pintype "bidirectional"))
    )
    (net (code "117") (name "unconnected-(IC1-PL2(T5)-Pad37)") (class "Default")
      (node (ref "IC1") (pin "37") (pinfunction "PL2(T5)_37") (pintype "bidirectional"))
    )
    (net (code "118") (name "unconnected-(IC1-PL3(OC5A)-Pad38)") (class "Default")
      (node (ref "IC1") (pin "38") (pinfunction "PL3(OC5A)_38") (pintype "bidirectional"))
    )
    (net (code "119") (name "unconnected-(IC1-PL4(OC5B)-Pad39)") (class "Default")
      (node (ref "IC1") (pin "39") (pinfunction "PL4(OC5B)_39") (pintype "bidirectional"))
    )
    (net (code "120") (name "unconnected-(U1A-QG-Pad6)") (class "Default")
      (node (ref "U1") (pin "6") (pinfunction "QG_6") (pintype "tri_state"))
    )
    (net (code "121") (name "unconnected-(U1A-QH-Pad7)") (class "Default")
      (node (ref "U1") (pin "7") (pinfunction "QH_7") (pintype "tri_state"))
    )
    (net (code "122") (name "unconnected-(U2A-QG-Pad6)") (class "Default")
      (node (ref "U2") (pin "6") (pinfunction "QG_6") (pintype "tri_state"))
    )
    (net (code "123") (name "unconnected-(U2A-QH-Pad7)") (class "Default")
      (node (ref "U2") (pin "7") (pinfunction "QH_7") (pintype "tri_state"))
    )
    (net (code "124") (name "unconnected-(U3A-QG-Pad6)") (class "Default")
      (node (ref "U3") (pin "6") (pinfunction "QG_6") (pintype "tri_state"))
    )
    (net (code "125") (name "unconnected-(U3A-QH*-Pad9)") (class "Default")
      (node (ref "U3") (pin "9") (pinfunction "QH*_9") (pintype "tri_state"))
    )
    (net (code "126") (name "unconnected-(U3A-QH-Pad7)") (class "Default")
      (node (ref "U3") (pin "7") (pinfunction "QH_7") (pintype "tri_state"))
    )
  )
)
